# CAN.net
KiCad netlist of a schematic drawn in Altium Designer
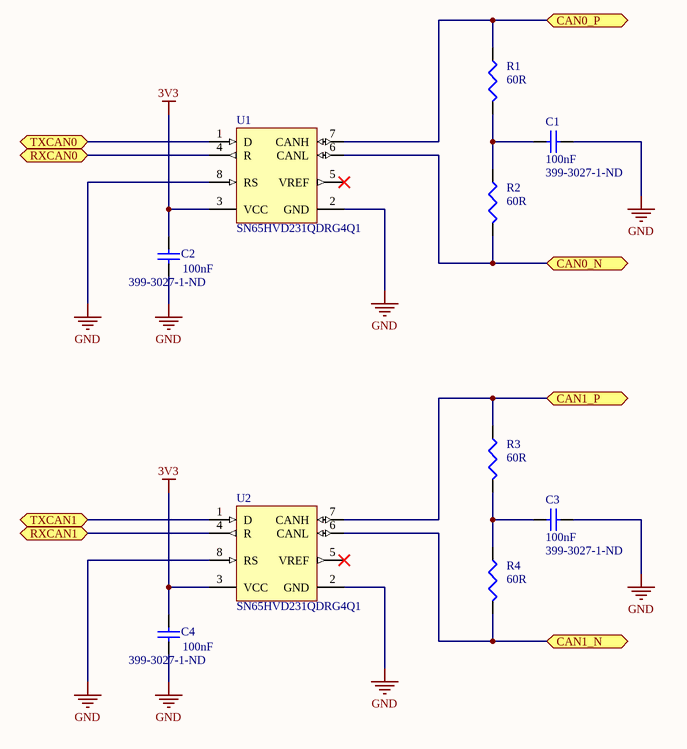
[diagram p0: CAN.SchDoc]

(export (version "E")
  (design (tool "Eeschema 10.0.6"))
  (components
    (comp (ref "C1")
      (value "100nF")
      (footprint "0402C-TBD")
      (description "Capacitor (Semiconductor SIM Model)")
      (fields
        (field (name "SUPPLIER PART NUMBER 1") "399-3027-1-ND")
        (field (name "MANUFACTURER") "Kemet")
        (field (name "MANUFACTURER PART NUMBER") "C0402C104K8PACTU")
        (field (name "PUBLISHER") "Altium Limited")
      )
      (libsource (lib "Miscellaneous Devices") (part "Cap Semi"))
    )
    (comp (ref "C2")
      (value "100nF")
      (footprint "0402C-TBD")
      (description "Capacitor (Semiconductor SIM Model)")
      (fields
        (field (name "SUPPLIER PART NUMBER 1") "399-3027-1-ND")
        (field (name "MANUFACTURER") "Kemet")
        (field (name "MANUFACTURER PART NUMBER") "C0402C104K8PACTU")
        (field (name "PUBLISHER") "Altium Limited")
      )
      (libsource (lib "Miscellaneous Devices") (part "Cap Semi"))
    )
    (comp (ref "C3")
      (value "100nF")
      (footprint "0402C-TBD")
      (description "Capacitor (Semiconductor SIM Model)")
      (fields
        (field (name "SUPPLIER PART NUMBER 1") "399-3027-1-ND")
        (field (name "MANUFACTURER") "Kemet")
        (field (name "MANUFACTURER PART NUMBER") "C0402C104K8PACTU")
        (field (name "PUBLISHER") "Altium Limited")
      )
      (libsource (lib "Miscellaneous Devices") (part "Cap Semi"))
    )
    (comp (ref "C4")
      (value "100nF")
      (footprint "0402C-TBD")
      (description "Capacitor (Semiconductor SIM Model)")
      (fields
        (field (name "SUPPLIER PART NUMBER 1") "399-3027-1-ND")
        (field (name "MANUFACTURER") "Kemet")
        (field (name "MANUFACTURER PART NUMBER") "C0402C104K8PACTU")
        (field (name "PUBLISHER") "Altium Limited")
      )
      (libsource (lib "Miscellaneous Devices") (part "Cap Semi"))
    )
    (comp (ref "R1")
      (value "60R")
      (footprint "0402R-TBD")
      (description "Resistor")
      (fields
        (field (name "DIGI-KEY PART NUMBER") "541-120GCT-ND")
        (field (name "Comment") "Res3")
        (field (name "PUBLISHER") "Altium Limited")
      )
      (libsource (lib "Miscellaneous Devices") (part "Res3"))
    )
    (comp (ref "R2")
      (value "60R")
      (footprint "0402R-TBD")
      (description "Resistor")
      (fields
        (field (name "DIGI-KEY PART NUMBER") "541-120GCT-ND")
        (field (name "Comment") "Res3")
        (field (name "PUBLISHER") "Altium Limited")
      )
      (libsource (lib "Miscellaneous Devices") (part "Res3"))
    )
    (comp (ref "R3")
      (value "60R")
      (footprint "0402R-TBD")
      (description "Resistor")
      (fields
        (field (name "DIGI-KEY PART NUMBER") "541-120GCT-ND")
        (field (name "Comment") "Res3")
        (field (name "PUBLISHER") "Altium Limited")
      )
      (libsource (lib "Miscellaneous Devices") (part "Res3"))
    )
    (comp (ref "R4")
      (value "60R")
      (footprint "0402R-TBD")
      (description "Resistor")
      (fields
        (field (name "DIGI-KEY PART NUMBER") "541-120GCT-ND")
        (field (name "Comment") "Res3")
        (field (name "PUBLISHER") "Altium Limited")
      )
      (libsource (lib "Miscellaneous Devices") (part "Res3"))
    )
    (comp (ref "U1")
      (value "SN65HVD231QDRG4Q1")
      (footprint "D8_M")
      (fields (field (name "MANUFACTURER") "Texas Instruments"))
      (libsource (lib "Altium Content Vault") (part "TI-SN65HVD231Q-Q1-SOIC_D-8"))
    )
    (comp (ref "U2")
      (value "SN65HVD231QDRG4Q1")
      (footprint "D8_M")
      (fields (field (name "MANUFACTURER") "Texas Instruments"))
      (libsource (lib "Altium Content Vault") (part "TI-SN65HVD231Q-Q1-SOIC_D-8"))
    )
  )
  (nets
    (net (code "1") (name "/CAN0_N") (class "Default")
      (node (ref "R2") (pin "2") (pinfunction "2_2") (pintype "passive"))
      (node (ref "U1") (pin "6") (pinfunction "CANL_6") (pintype "bidirectional"))
    )
    (net (code "2") (name "/CAN0_P") (class "Default")
      (node (ref "R1") (pin "1") (pinfunction "1_1") (pintype "passive"))
      (node (ref "U1") (pin "7") (pinfunction "CANH_7") (pintype "bidirectional"))
    )
    (net (code "3") (name "/CAN1_N") (class "Default")
      (node (ref "R4") (pin "2") (pinfunction "2_2") (pintype "passive"))
      (node (ref "U2") (pin "6") (pinfunction "CANL_6") (pintype "bidirectional"))
    )
    (net (code "4") (name "/CAN1_P") (class "Default")
      (node (ref "R3") (pin "1") (pinfunction "1_1") (pintype "passive"))
      (node (ref "U2") (pin "7") (pinfunction "CANH_7") (pintype "bidirectional"))
    )
    (net (code "5") (name "/RXCAN0") (class "Default")
      (node (ref "U1") (pin "4") (pinfunction "R_4") (pintype "output"))
    )
    (net (code "6") (name "/RXCAN1") (class "Default")
      (node (ref "U2") (pin "4") (pinfunction "R_4") (pintype "output"))
    )
    (net (code "7") (name "/TXCAN0") (class "Default")
      (node (ref "U1") (pin "1") (pinfunction "D_1") (pintype "input"))
    )
    (net (code "8") (name "/TXCAN1") (class "Default")
      (node (ref "U2") (pin "1") (pinfunction "D_1") (pintype "input"))
    )
    (net (code "9") (name "3V3") (class "Default")
      (node (ref "C2") (pin "1") (pinfunction "1_1") (pintype "passive"))
      (node (ref "C4") (pin "1") (pinfunction "1_1") (pintype "passive"))
      (node (ref "U1") (pin "3") (pinfunction "VCC_3") (pintype "power_in"))
      (node (ref "U2") (pin "3") (pinfunction "VCC_3") (pintype "power_in"))
    )
    (net (code "10") (name "GND") (class "Default")
      (node (ref "C1") (pin "2") (pinfunction "2_2") (pintype "passive"))
      (node (ref "C2") (pin "2") (pinfunction "2_2") (pintype "passive"))
      (node (ref "C3") (pin "2") (pinfunction "2_2") (pintype "passive"))
      (node (ref "C4") (pin "2") (pinfunction "2_2") (pintype "passive"))
      (node (ref "U1") (pin "2") (pinfunction "GND_2") (pintype "power_in"))
      (node (ref "U1") (pin "8") (pinfunction "RS_8") (pintype "input"))
      (node (ref "U2") (pin "2") (pinfunction "GND_2") (pintype "power_in"))
      (node (ref "U2") (pin "8") (pinfunction "RS_8") (pintype "input"))
    )
    (net (code "11") (name "Net-(C1-Pad1)") (class "Default")
      (node (ref "C1") (pin "1") (pinfunction "1_1") (pintype "passive"))
      (node (ref "R1") (pin "2") (pinfunction "2_2") (pintype "passive"))
      (node (ref "R2") (pin "1") (pinfunction "1_1") (pintype "passive"))
    )
    (net (code "12") (name "Net-(C3-Pad1)") (class "Default")
      (node (ref "C3") (pin "1") (pinfunction "1_1") (pintype "passive"))
      (node (ref "R3") (pin "2") (pinfunction "2_2") (pintype "passive"))
      (node (ref "R4") (pin "1") (pinfunction "1_1") (pintype "passive"))
    )
    (net (code "13") (name "unconnected-(U1-VREF-Pad5)") (class "Default")
      (node (ref "U1") (pin "5") (pinfunction "VREF_5") (pintype "output+no_connect"))
    )
    (net (code "14") (name "unconnected-(U2-VREF-Pad5)") (class "Default")
      (node (ref "U2") (pin "5") (pinfunction "VREF_5") (pintype "output+no_connect"))
    )
  )
)
